# homenodeInline.net
KiCad netlist of a schematic drawn in EAGLE
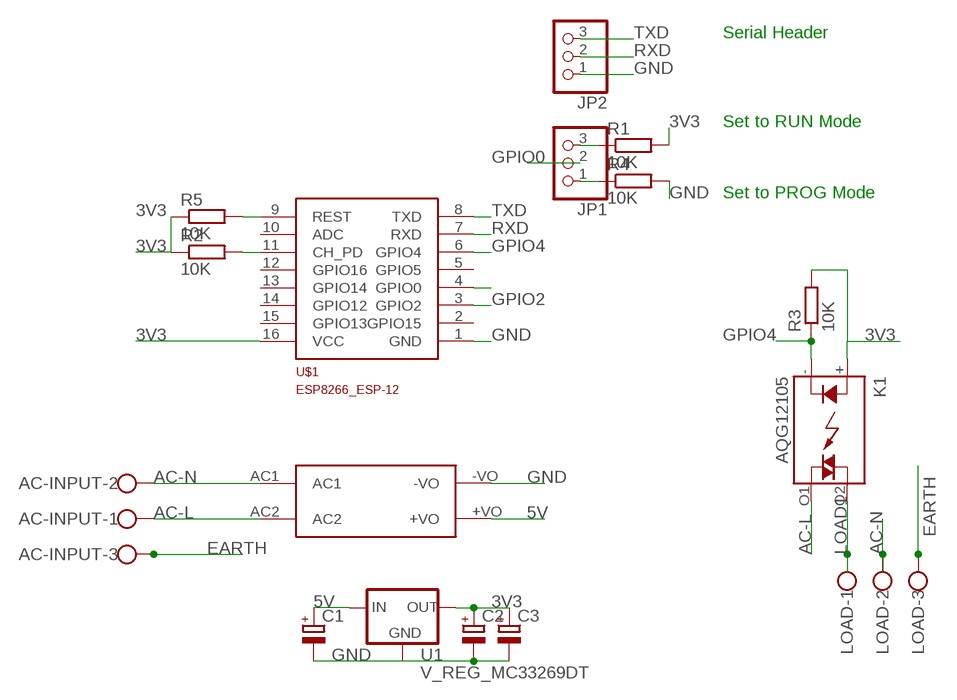
[diagram p0: schematic, sheet 1]

(export (version "E")
  (design (tool "Eeschema 10.0.6"))
  (components
    (comp (ref "AC-INPUT")
      (value "W237-103")
      (footprint "eagle-import:W237-103")
      (fields (field (name "MPN") "237-103"))
      (libsource (lib "eagle-import") (part "W237-103"))
    )
    (comp (ref "C1")
      (value "CPOL-EUC")
      (footprint "eagle-import:PANASONIC_C")
      (libsource (lib "eagle-import") (part "CPOL-EUC"))
    )
    (comp (ref "C2")
      (value "CPOL-EUC")
      (footprint "eagle-import:PANASONIC_C")
      (libsource (lib "eagle-import") (part "CPOL-EUC"))
    )
    (comp (ref "C3")
      (value "CPOL-EUC")
      (footprint "eagle-import:PANASONIC_C")
      (libsource (lib "eagle-import") (part "CPOL-EUC"))
    )
    (comp (ref "JP1")
      (value "PINHD-1X3")
      (footprint "eagle-import:1X03")
      (libsource (lib "eagle-import") (part "PINHD-1X3"))
    )
    (comp (ref "JP2")
      (value "PINHD-1X3")
      (footprint "eagle-import:1X03")
      (libsource (lib "eagle-import") (part "PINHD-1X3"))
    )
    (comp (ref "K1")
      (value "AQG12105")
      (footprint "eagle-import:AQG")
      (fields (field (name "MF") "AROMAT/ MATSUSHITA"))
      (libsource (lib "eagle-import") (part "AQG12105"))
    )
    (comp (ref "LOAD")
      (value "W237-103")
      (footprint "eagle-import:W237-103")
      (fields (field (name "MPN") "237-103"))
      (libsource (lib "eagle-import") (part "W237-103"))
    )
    (comp (ref "R1")
      (value "10K")
      (footprint "eagle-import:M1206")
      (libsource (lib "eagle-import") (part "R-EU_M1206"))
    )
    (comp (ref "R2")
      (value "10K")
      (footprint "eagle-import:M1206")
      (libsource (lib "eagle-import") (part "R-EU_M1206"))
    )
    (comp (ref "R3")
      (value "10K")
      (footprint "eagle-import:M1206")
      (libsource (lib "eagle-import") (part "R-EU_M1206"))
    )
    (comp (ref "R4")
      (value "10K")
      (footprint "eagle-import:M1206")
      (libsource (lib "eagle-import") (part "R-EU_M1206"))
    )
    (comp (ref "R5")
      (value "10K")
      (footprint "eagle-import:M1206")
      (libsource (lib "eagle-import") (part "R-EU_M1206"))
    )
    (comp (ref "U$1")
      (value "ESP8266_ESP-12")
      (footprint "eagle-import:ESP8266-ESP12")
      (libsource (lib "eagle-import") (part "ESP8266_ESP-12"))
    )
    (comp (ref "U$4")
      (value "HLK-PM01")
      (footprint "eagle-import:HLK-PM01")
      (libsource (lib "eagle-import") (part "HLK-PM01"))
    )
    (comp (ref "U1")
      (value "V_REG_MC33269DT")
      (footprint "eagle-import:DPAK")
      (libsource (lib "eagle-import") (part "V_REG_MC33269DT"))
    )
  )
  (nets
    (net (code "1") (name "/3V3") (class "Default")
      (node (ref "C2") (pin "+") (pinfunction "+_+") (pintype "passive"))
      (node (ref "C3") (pin "+") (pinfunction "+_+") (pintype "passive"))
      (node (ref "K1") (pin "+") (pinfunction "A_+") (pintype "passive"))
      (node (ref "R1") (pin "2") (pinfunction "2_2") (pintype "passive"))
      (node (ref "R2") (pin "1") (pinfunction "1_1") (pintype "passive"))
      (node (ref "R3") (pin "2") (pinfunction "2_2") (pintype "passive"))
      (node (ref "R5") (pin "1") (pinfunction "1_1") (pintype "passive"))
      (node (ref "U$1") (pin "16") (pinfunction "VCC_16") (pintype "bidirectional"))
      (node (ref "U1") (pin "4") (pinfunction "OUT_4") (pintype "output"))
    )
    (net (code "2") (name "/5V") (class "Default")
      (node (ref "C1") (pin "+") (pinfunction "+_+") (pintype "passive"))
      (node (ref "U$4") (pin "+VO") (pinfunction "+VO_+VO") (pintype "bidirectional"))
      (node (ref "U1") (pin "3") (pinfunction "IN_3") (pintype "input"))
    )
    (net (code "3") (name "/AC-L") (class "Default")
      (node (ref "AC-INPUT") (pin "1") (pinfunction "KL_1") (pintype "passive"))
      (node (ref "K1") (pin "O1") (pinfunction "DS2_O1") (pintype "passive"))
      (node (ref "U$4") (pin "AC2") (pinfunction "AC2_AC2") (pintype "bidirectional"))
    )
    (net (code "4") (name "/AC-N") (class "Default")
      (node (ref "AC-INPUT") (pin "2") (pinfunction "KL_2") (pintype "passive"))
      (node (ref "LOAD") (pin "2") (pinfunction "KL_2") (pintype "passive"))
      (node (ref "U$4") (pin "AC1") (pinfunction "AC1_AC1") (pintype "bidirectional"))
    )
    (net (code "5") (name "/EARTH") (class "Default")
      (node (ref "AC-INPUT") (pin "3") (pinfunction "KL_3") (pintype "passive"))
      (node (ref "LOAD") (pin "3") (pinfunction "KL_3") (pintype "passive"))
    )
    (net (code "6") (name "/GND") (class "Default")
      (node (ref "C1") (pin "-") (pinfunction "-_-") (pintype "passive"))
      (node (ref "C2") (pin "-") (pinfunction "-_-") (pintype "passive"))
      (node (ref "C3") (pin "-") (pinfunction "-_-") (pintype "passive"))
      (node (ref "JP2") (pin "1") (pinfunction "1_1") (pintype "passive"))
      (node (ref "R4") (pin "2") (pinfunction "2_2") (pintype "passive"))
      (node (ref "U$1") (pin "1") (pinfunction "GND_1") (pintype "bidirectional"))
      (node (ref "U$4") (pin "-VO") (pinfunction "-VO_-VO") (pintype "bidirectional"))
      (node (ref "U1") (pin "1") (pinfunction "GND_1") (pintype "input"))
    )
    (net (code "7") (name "/GPIO0") (class "Default")
      (node (ref "JP1") (pin "2") (pinfunction "2_2") (pintype "passive"))
      (node (ref "U$1") (pin "4") (pinfunction "GPIO0_4") (pintype "bidirectional"))
    )
    (net (code "8") (name "/GPIO2") (class "Default")
      (node (ref "U$1") (pin "3") (pinfunction "GPIO2_3") (pintype "bidirectional"))
    )
    (net (code "9") (name "/GPIO4") (class "Default")
      (node (ref "K1") (pin "-") (pinfunction "K_-") (pintype "passive"))
      (node (ref "R3") (pin "1") (pinfunction "1_1") (pintype "passive"))
      (node (ref "U$1") (pin "6") (pinfunction "GPIO4_6") (pintype "bidirectional"))
    )
    (net (code "10") (name "/LOAD1") (class "Default")
      (node (ref "K1") (pin "O2") (pinfunction "DS1_O2") (pintype "passive"))
      (node (ref "LOAD") (pin "1") (pinfunction "KL_1") (pintype "passive"))
    )
    (net (code "11") (name "/RXD") (class "Default")
      (node (ref "JP2") (pin "2") (pinfunction "2_2") (pintype "passive"))
      (node (ref "U$1") (pin "7") (pinfunction "RXD_7") (pintype "bidirectional"))
    )
    (net (code "12") (name "/TXD") (class "Default")
      (node (ref "JP2") (pin "3") (pinfunction "3_3") (pintype "passive"))
      (node (ref "U$1") (pin "8") (pinfunction "TXD_8") (pintype "bidirectional"))
    )
    (net (code "13") (name "Net-(JP1-Pad1)") (class "Default")
      (node (ref "JP1") (pin "1") (pinfunction "1_1") (pintype "passive"))
      (node (ref "R4") (pin "1") (pinfunction "1_1") (pintype "passive"))
    )
    (net (code "14") (name "Net-(JP1-Pad3)") (class "Default")
      (node (ref "JP1") (pin "3") (pinfunction "3_3") (pintype "passive"))
      (node (ref "R1") (pin "1") (pinfunction "1_1") (pintype "passive"))
    )
    (net (code "15") (name "Net-(U$1-CH_PD)") (class "Default")
      (node (ref "R2") (pin "2") (pinfunction "2_2") (pintype "passive"))
      (node (ref "U$1") (pin "11") (pinfunction "CH_PD_11") (pintype "bidirectional"))
    )
    (net (code "16") (name "Net-(U$1-REST)") (class "Default")
      (node (ref "R5") (pin "2") (pinfunction "2_2") (pintype "passive"))
      (node (ref "U$1") (pin "9") (pinfunction "REST_9") (pintype "bidirectional"))
    )
    (net (code "17") (name "unconnected-(U$1-ADC-Pad10)") (class "Default")
      (node (ref "U$1") (pin "10") (pinfunction "ADC_10") (pintype "bidirectional"))
    )
    (net (code "18") (name "unconnected-(U$1-GPIO5-Pad5)") (class "Default")
      (node (ref "U$1") (pin "5") (pinfunction "GPIO5_5") (pintype "bidirectional"))
    )
    (net (code "19") (name "unconnected-(U$1-GPIO12-Pad14)") (class "Default")
      (node (ref "U$1") (pin "14") (pinfunction "GPIO12_14") (pintype "bidirectional"))
    )
    (net (code "20") (name "unconnected-(U$1-GPIO13-Pad15)") (class "Default")
      (node (ref "U$1") (pin "15") (pinfunction "GPIO13_15") (pintype "bidirectional"))
    )
    (net (code "21") (name "unconnected-(U$1-GPIO14-Pad13)") (class "Default")
      (node (ref "U$1") (pin "13") (pinfunction "GPIO14_13") (pintype "bidirectional"))
    )
    (net (code "22") (name "unconnected-(U$1-GPIO15-Pad2)") (class "Default")
      (node (ref "U$1") (pin "2") (pinfunction "GPIO15_2") (pintype "bidirectional"))
    )
    (net (code "23") (name "unconnected-(U$1-GPIO16-Pad12)") (class "Default")
      (node (ref "U$1") (pin "12") (pinfunction "GPIO16_12") (pintype "bidirectional"))
    )
  )
)
